# WW-11.net
KiCad netlist of a schematic drawn in EAGLE
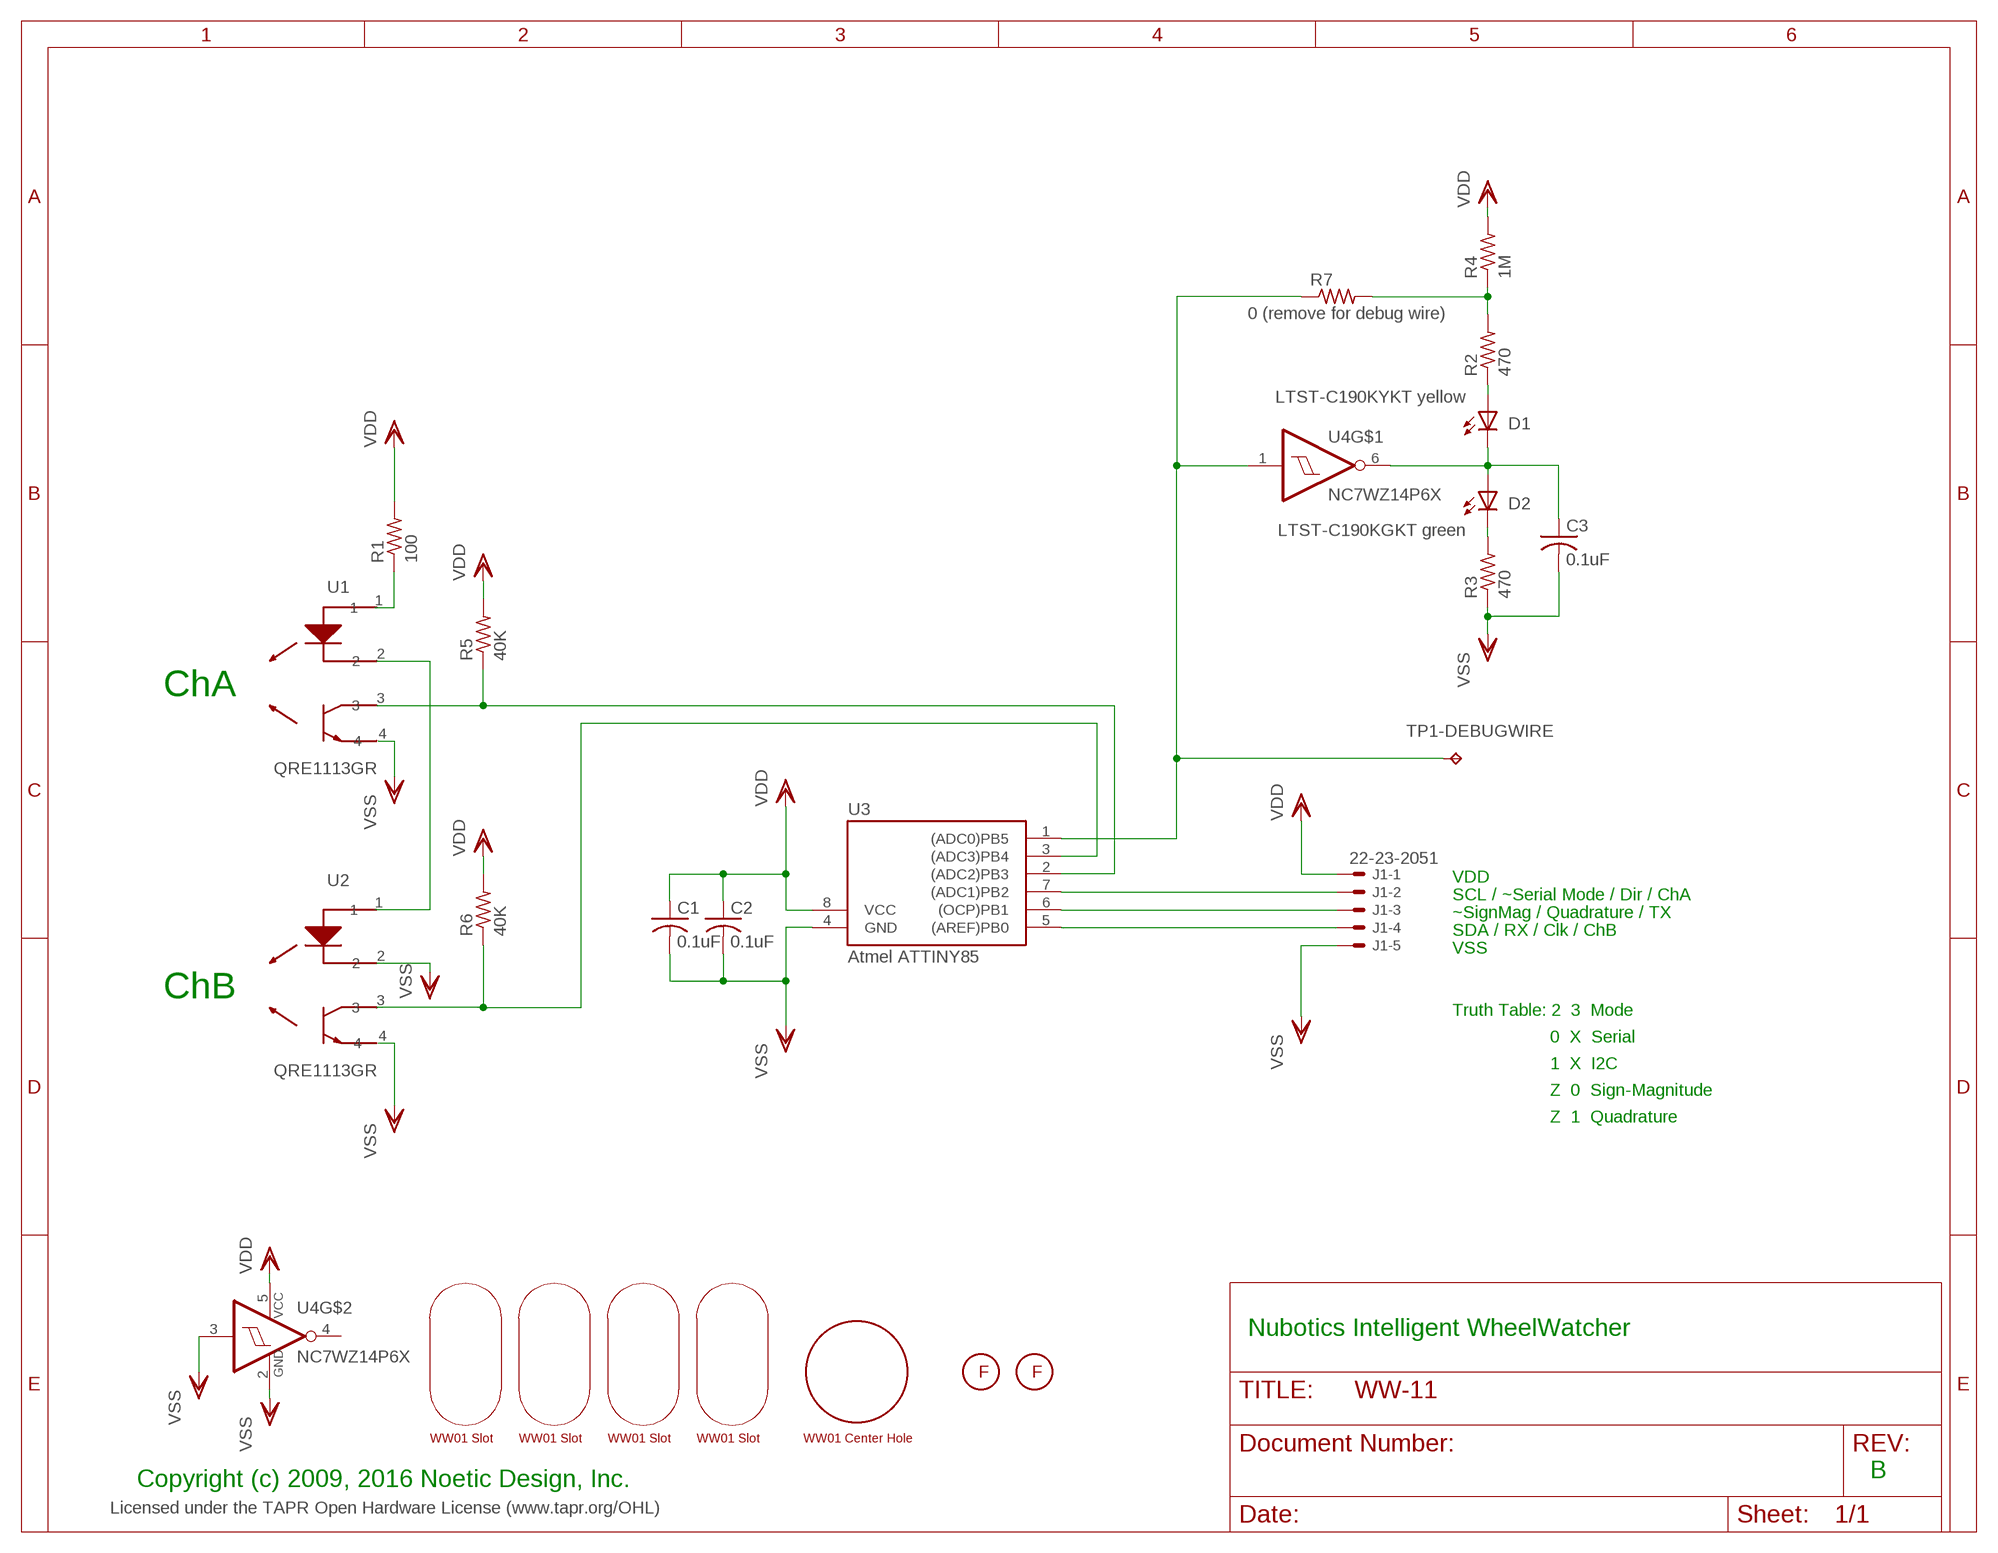
[diagram p0: schematic, sheet 1]

(export (version "E")
  (design (tool "Eeschema 10.0.6"))
  (components
    (comp (ref "C1")
      (value "0.1uF")
      (footprint "eagle-import:C0603")
      (libsource (lib "eagle-import") (part "resistor_C-USC0603"))
    )
    (comp (ref "C2")
      (value "0.1uF")
      (footprint "eagle-import:C0603")
      (libsource (lib "eagle-import") (part "resistor_C-USC0603"))
    )
    (comp (ref "C3")
      (value "0.1uF")
      (footprint "eagle-import:C0603")
      (libsource (lib "eagle-import") (part "C-USC0603"))
    )
    (comp (ref "D1")
      (value "LTST-C190KYKT yellow")
      (footprint "eagle-import:CHIP-LED0603")
      (libsource (lib "eagle-import") (part "LEDCHIP-LED0603"))
    )
    (comp (ref "D2")
      (value "LTST-C190KGKT green")
      (footprint "eagle-import:CHIP-LED0603")
      (libsource (lib "eagle-import") (part "LEDCHIP-LED0603"))
    )
    (comp (ref "FM1")
      (value "FIDUCIAL2MMCIRCLE")
      (footprint "eagle-import:FIDUCIAL_2MMCIRCLE")
      (libsource (lib "eagle-import") (part "FIDUCIAL2MMCIRCLE"))
    )
    (comp (ref "FM2")
      (value "FIDUCIAL2MMCIRCLE")
      (footprint "eagle-import:FIDUCIAL_2MMCIRCLE")
      (libsource (lib "eagle-import") (part "FIDUCIAL2MMCIRCLE"))
    )
    (comp (ref "J1")
      (value "22-23-2051")
      (footprint "eagle-import:22-23-2051")
      (libsource (lib "eagle-import") (part "22-23-2051"))
    )
    (comp (ref "R1")
      (value "100")
      (footprint "eagle-import:R0603")
      (libsource (lib "eagle-import") (part "resistor_R-US_R0603"))
    )
    (comp (ref "R2")
      (value "470")
      (footprint "eagle-import:R0603")
      (libsource (lib "eagle-import") (part "resistor_R-US_R0603"))
    )
    (comp (ref "R3")
      (value "470")
      (footprint "eagle-import:R0603")
      (libsource (lib "eagle-import") (part "resistor_R-US_R0603"))
    )
    (comp (ref "R4")
      (value "1M")
      (footprint "eagle-import:R0603")
      (libsource (lib "eagle-import") (part "R-US_R0603"))
    )
    (comp (ref "R5")
      (value "40K")
      (footprint "eagle-import:R0603")
      (libsource (lib "eagle-import") (part "resistor_R-US_R0603"))
    )
    (comp (ref "R6")
      (value "40K")
      (footprint "eagle-import:R0603")
      (libsource (lib "eagle-import") (part "resistor_R-US_R0603"))
    )
    (comp (ref "R7")
      (value "0 (remove for debug wire)")
      (footprint "eagle-import:R0603")
      (libsource (lib "eagle-import") (part "R-US_R0603"))
    )
    (comp (ref "TP1-DEBUGWIRE")
      (value "DEBUG WIRE")
      (footprint "eagle-import:B1,27")
      (libsource (lib "eagle-import") (part "TPB1,27"))
    )
    (comp (ref "U$1")
      (value "WW-01SLOT")
      (footprint "eagle-import:WW01-SLOT")
      (libsource (lib "eagle-import") (part "WW-01SLOT"))
    )
    (comp (ref "U$2")
      (value "WW-01SLOT")
      (footprint "eagle-import:WW01-SLOT")
      (libsource (lib "eagle-import") (part "WW-01SLOT"))
    )
    (comp (ref "U$3")
      (value "WW-01SLOT")
      (footprint "eagle-import:WW01-SLOT")
      (libsource (lib "eagle-import") (part "WW-01SLOT"))
    )
    (comp (ref "U$4")
      (value "WW-01SLOT")
      (footprint "eagle-import:WW01-SLOT")
      (libsource (lib "eagle-import") (part "WW-01SLOT"))
    )
    (comp (ref "U$5")
      (value "WW01-CENTER")
      (footprint "eagle-import:WW01-CENTER")
      (libsource (lib "eagle-import") (part "WW01-CENTER"))
    )
    (comp (ref "U1")
      (value "QRE1113GR")
      (footprint "eagle-import:4TSOP")
      (fields (field (name "PARTNUMBER") "03-0261"))
      (libsource (lib "eagle-import") (part "QRE1113GR"))
    )
    (comp (ref "U2")
      (value "QRE1113GR")
      (footprint "eagle-import:4TSOP")
      (fields (field (name "PARTNUMBER") "03-0261"))
      (libsource (lib "eagle-import") (part "QRE1113GR"))
    )
    (comp (ref "U3")
      (value "Atmel ATTINY85")
      (footprint "eagle-import:SOIC8")
      (libsource (lib "eagle-import") (part "TINY85S"))
    )
    (comp (ref "U4")
      (value "NC7WZ14P6X")
      (footprint "eagle-import:SOT65P210X110-6AN_SC88_SC70-6")
      (libsource (lib "eagle-import") (part "NC7W14P6XZ"))
    )
  )
  (nets
    (net (code "1") (name "Net-(D1-PadA)") (class "Default")
      (node (ref "D1") (pin "A") (pinfunction "A_A") (pintype "passive"))
      (node (ref "R2") (pin "1") (pinfunction "1_1") (pintype "passive"))
    )
    (net (code "2") (name "Net-(D2-PadC)") (class "Default")
      (node (ref "D2") (pin "C") (pinfunction "C_C") (pintype "passive"))
      (node (ref "R3") (pin "2") (pinfunction "2_2") (pintype "passive"))
    )
    (net (code "3") (name "Net-(J1B-S)") (class "Default")
      (node (ref "J1") (pin "2") (pinfunction "S_2") (pintype "passive"))
      (node (ref "U3") (pin "7") (pinfunction "(ADC1)PB2_7") (pintype "bidirectional"))
    )
    (net (code "4") (name "Net-(J1C-S)") (class "Default")
      (node (ref "J1") (pin "3") (pinfunction "S_3") (pintype "passive"))
      (node (ref "U3") (pin "6") (pinfunction "(OCP)PB1_6") (pintype "bidirectional"))
    )
    (net (code "5") (name "Net-(J1D-S)") (class "Default")
      (node (ref "J1") (pin "4") (pinfunction "S_4") (pintype "passive"))
      (node (ref "U3") (pin "5") (pinfunction "(AREF)PB0_5") (pintype "bidirectional"))
    )
    (net (code "6") (name "Net-(R1-Pad1)") (class "Default")
      (node (ref "R1") (pin "1") (pinfunction "1_1") (pintype "passive"))
      (node (ref "U1") (pin "1") (pinfunction "1_1") (pintype "bidirectional"))
    )
    (net (code "7") (name "Net-(R2-Pad2)") (class "Default")
      (node (ref "R2") (pin "2") (pinfunction "2_2") (pintype "passive"))
      (node (ref "R4") (pin "1") (pinfunction "1_1") (pintype "passive"))
      (node (ref "R7") (pin "2") (pinfunction "2_2") (pintype "passive"))
    )
    (net (code "8") (name "Net-(TP1-DEBUGWIRE-TP)") (class "Default")
      (node (ref "R7") (pin "1") (pinfunction "1_1") (pintype "passive"))
      (node (ref "TP1-DEBUGWIRE") (pin "PP") (pinfunction "TP_PP") (pintype "input"))
      (node (ref "U3") (pin "1") (pinfunction "(ADC0)PB5_1") (pintype "bidirectional"))
      (node (ref "U4") (pin "1") (pinfunction "I_1") (pintype "input"))
    )
    (net (code "9") (name "Net-(U1-Pad2)") (class "Default")
      (node (ref "U1") (pin "2") (pinfunction "2_2") (pintype "bidirectional"))
      (node (ref "U2") (pin "1") (pinfunction "1_1") (pintype "bidirectional"))
    )
    (net (code "10") (name "Net-(U3-(ADC2)PB3)") (class "Default")
      (node (ref "R5") (pin "1") (pinfunction "1_1") (pintype "passive"))
      (node (ref "U1") (pin "3") (pinfunction "3_3") (pintype "bidirectional"))
      (node (ref "U3") (pin "2") (pinfunction "(ADC2)PB3_2") (pintype "bidirectional"))
    )
    (net (code "11") (name "Net-(U3-(ADC3)PB4)") (class "Default")
      (node (ref "R6") (pin "1") (pinfunction "1_1") (pintype "passive"))
      (node (ref "U2") (pin "3") (pinfunction "3_3") (pintype "bidirectional"))
      (node (ref "U3") (pin "3") (pinfunction "(ADC3)PB4_3") (pintype "bidirectional"))
    )
    (net (code "12") (name "Net-(U4A-O)") (class "Default")
      (node (ref "C3") (pin "1") (pinfunction "1_1") (pintype "passive"))
      (node (ref "D1") (pin "C") (pinfunction "C_C") (pintype "passive"))
      (node (ref "D2") (pin "A") (pinfunction "A_A") (pintype "passive"))
      (node (ref "U4") (pin "6") (pinfunction "O_6") (pintype "output"))
    )
    (net (code "13") (name "VDD") (class "Default")
      (node (ref "C1") (pin "1") (pinfunction "1_1") (pintype "passive"))
      (node (ref "C2") (pin "1") (pinfunction "1_1") (pintype "passive"))
      (node (ref "J1") (pin "1") (pinfunction "S_1") (pintype "passive"))
      (node (ref "R1") (pin "2") (pinfunction "2_2") (pintype "passive"))
      (node (ref "R4") (pin "2") (pinfunction "2_2") (pintype "passive"))
      (node (ref "R5") (pin "2") (pinfunction "2_2") (pintype "passive"))
      (node (ref "R6") (pin "2") (pinfunction "2_2") (pintype "passive"))
      (node (ref "U3") (pin "8") (pinfunction "VCC_8") (pintype "power_in"))
      (node (ref "U4") (pin "5") (pinfunction "VCC_5") (pintype "power_in"))
    )
    (net (code "14") (name "VSS") (class "Default")
      (node (ref "C1") (pin "2") (pinfunction "2_2") (pintype "passive"))
      (node (ref "C2") (pin "2") (pinfunction "2_2") (pintype "passive"))
      (node (ref "C3") (pin "2") (pinfunction "2_2") (pintype "passive"))
      (node (ref "J1") (pin "5") (pinfunction "S_5") (pintype "passive"))
      (node (ref "R3") (pin "1") (pinfunction "1_1") (pintype "passive"))
      (node (ref "U1") (pin "4") (pinfunction "4_4") (pintype "bidirectional"))
      (node (ref "U2") (pin "2") (pinfunction "2_2") (pintype "bidirectional"))
      (node (ref "U2") (pin "4") (pinfunction "4_4") (pintype "bidirectional"))
      (node (ref "U3") (pin "4") (pinfunction "GND_4") (pintype "power_in"))
      (node (ref "U4") (pin "2") (pinfunction "GND_2") (pintype "power_in"))
      (node (ref "U4") (pin "3") (pinfunction "I_3") (pintype "input"))
    )
    (net (code "15") (name "unconnected-(U4B-O-Pad4)") (class "Default")
      (node (ref "U4") (pin "4") (pinfunction "O_4") (pintype "output"))
    )
  )
)
